# USB_Power_Adapter_V2.net
KiCad netlist of a schematic drawn in EAGLE
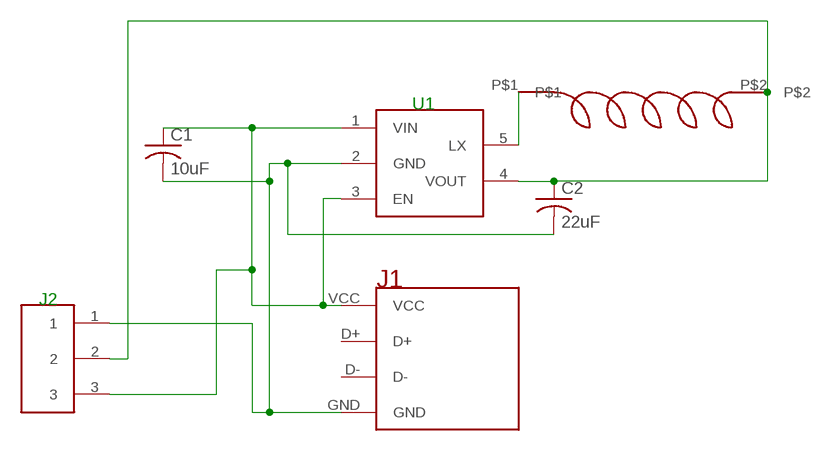
[diagram p0: schematic, sheet 1]

(export (version "E")
  (design (tool "Eeschema 10.0.6"))
  (components
    (comp (ref "C1")
      (value "10uF")
      (footprint "eagle-import:C0805K")
      (libsource (lib "eagle-import") (part "C-USC0805K"))
    )
    (comp (ref "C2")
      (value "22uF")
      (footprint "eagle-import:C0805K")
      (libsource (lib "eagle-import") (part "C-USC0805K"))
    )
    (comp (ref "J1")
      (value "MICROUSBMICROUSB_THRU")
      (footprint "eagle-import:MICROUSB_THRU")
      (libsource (lib "eagle-import") (part "MICROUSBMICROUSB_THRU"))
    )
    (comp (ref "U$1")
      (value "SMDINDUCTOR")
      (footprint "eagle-import:SMDINDUCTOR")
      (libsource (lib "eagle-import") (part "SMDINDUCTOR"))
    )
    (comp (ref "U$2")
      (value "DF3_1X3")
      (footprint "eagle-import:DF3_1X3")
      (libsource (lib "eagle-import") (part "DF3_1X3"))
    )
    (comp (ref "U1")
      (value "SC189")
      (footprint "eagle-import:SC189")
      (libsource (lib "eagle-import") (part "SC189"))
    )
  )
  (nets
    (net (code "1") (name "Net-(U1-EN)") (class "Default")
      (node (ref "C1") (pin "1") (pinfunction "1_1") (pintype "passive"))
      (node (ref "J1") (pin "VCC") (pinfunction "VCC_VCC") (pintype "bidirectional"))
      (node (ref "U$2") (pin "3") (pinfunction "3_3") (pintype "bidirectional"))
      (node (ref "U1") (pin "1") (pinfunction "VIN_1") (pintype "bidirectional"))
      (node (ref "U1") (pin "3") (pinfunction "EN_3") (pintype "bidirectional"))
    )
    (net (code "2") (name "Net-(U1-GND)") (class "Default")
      (node (ref "C1") (pin "2") (pinfunction "2_2") (pintype "passive"))
      (node (ref "C2") (pin "2") (pinfunction "2_2") (pintype "passive"))
      (node (ref "J1") (pin "GND") (pinfunction "GND_GND") (pintype "bidirectional"))
      (node (ref "U$2") (pin "1") (pinfunction "1_1") (pintype "bidirectional"))
      (node (ref "U1") (pin "2") (pinfunction "GND_2") (pintype "bidirectional"))
    )
    (net (code "3") (name "Net-(U1-LX)") (class "Default")
      (node (ref "U$1") (pin "P$1") (pinfunction "P$1_P$1") (pintype "bidirectional"))
      (node (ref "U1") (pin "5") (pinfunction "LX_5") (pintype "bidirectional"))
    )
    (net (code "4") (name "Net-(U1-VOUT)") (class "Default")
      (node (ref "C2") (pin "1") (pinfunction "1_1") (pintype "passive"))
      (node (ref "U$1") (pin "P$2") (pinfunction "P$2_P$2") (pintype "bidirectional"))
      (node (ref "U$2") (pin "2") (pinfunction "2_2") (pintype "bidirectional"))
      (node (ref "U1") (pin "4") (pinfunction "VOUT_4") (pintype "bidirectional"))
    )
    (net (code "5") (name "unconnected-(J1-PadD+)") (class "Default")
      (node (ref "J1") (pin "D+") (pinfunction "D+_D+") (pintype "bidirectional"))
    )
    (net (code "6") (name "unconnected-(J1-PadD-)") (class "Default")
      (node (ref "J1") (pin "D-") (pinfunction "D-_D-") (pintype "bidirectional"))
    )
  )
)
